# esp32_ics.net
KiCad netlist of a schematic drawn in EAGLE
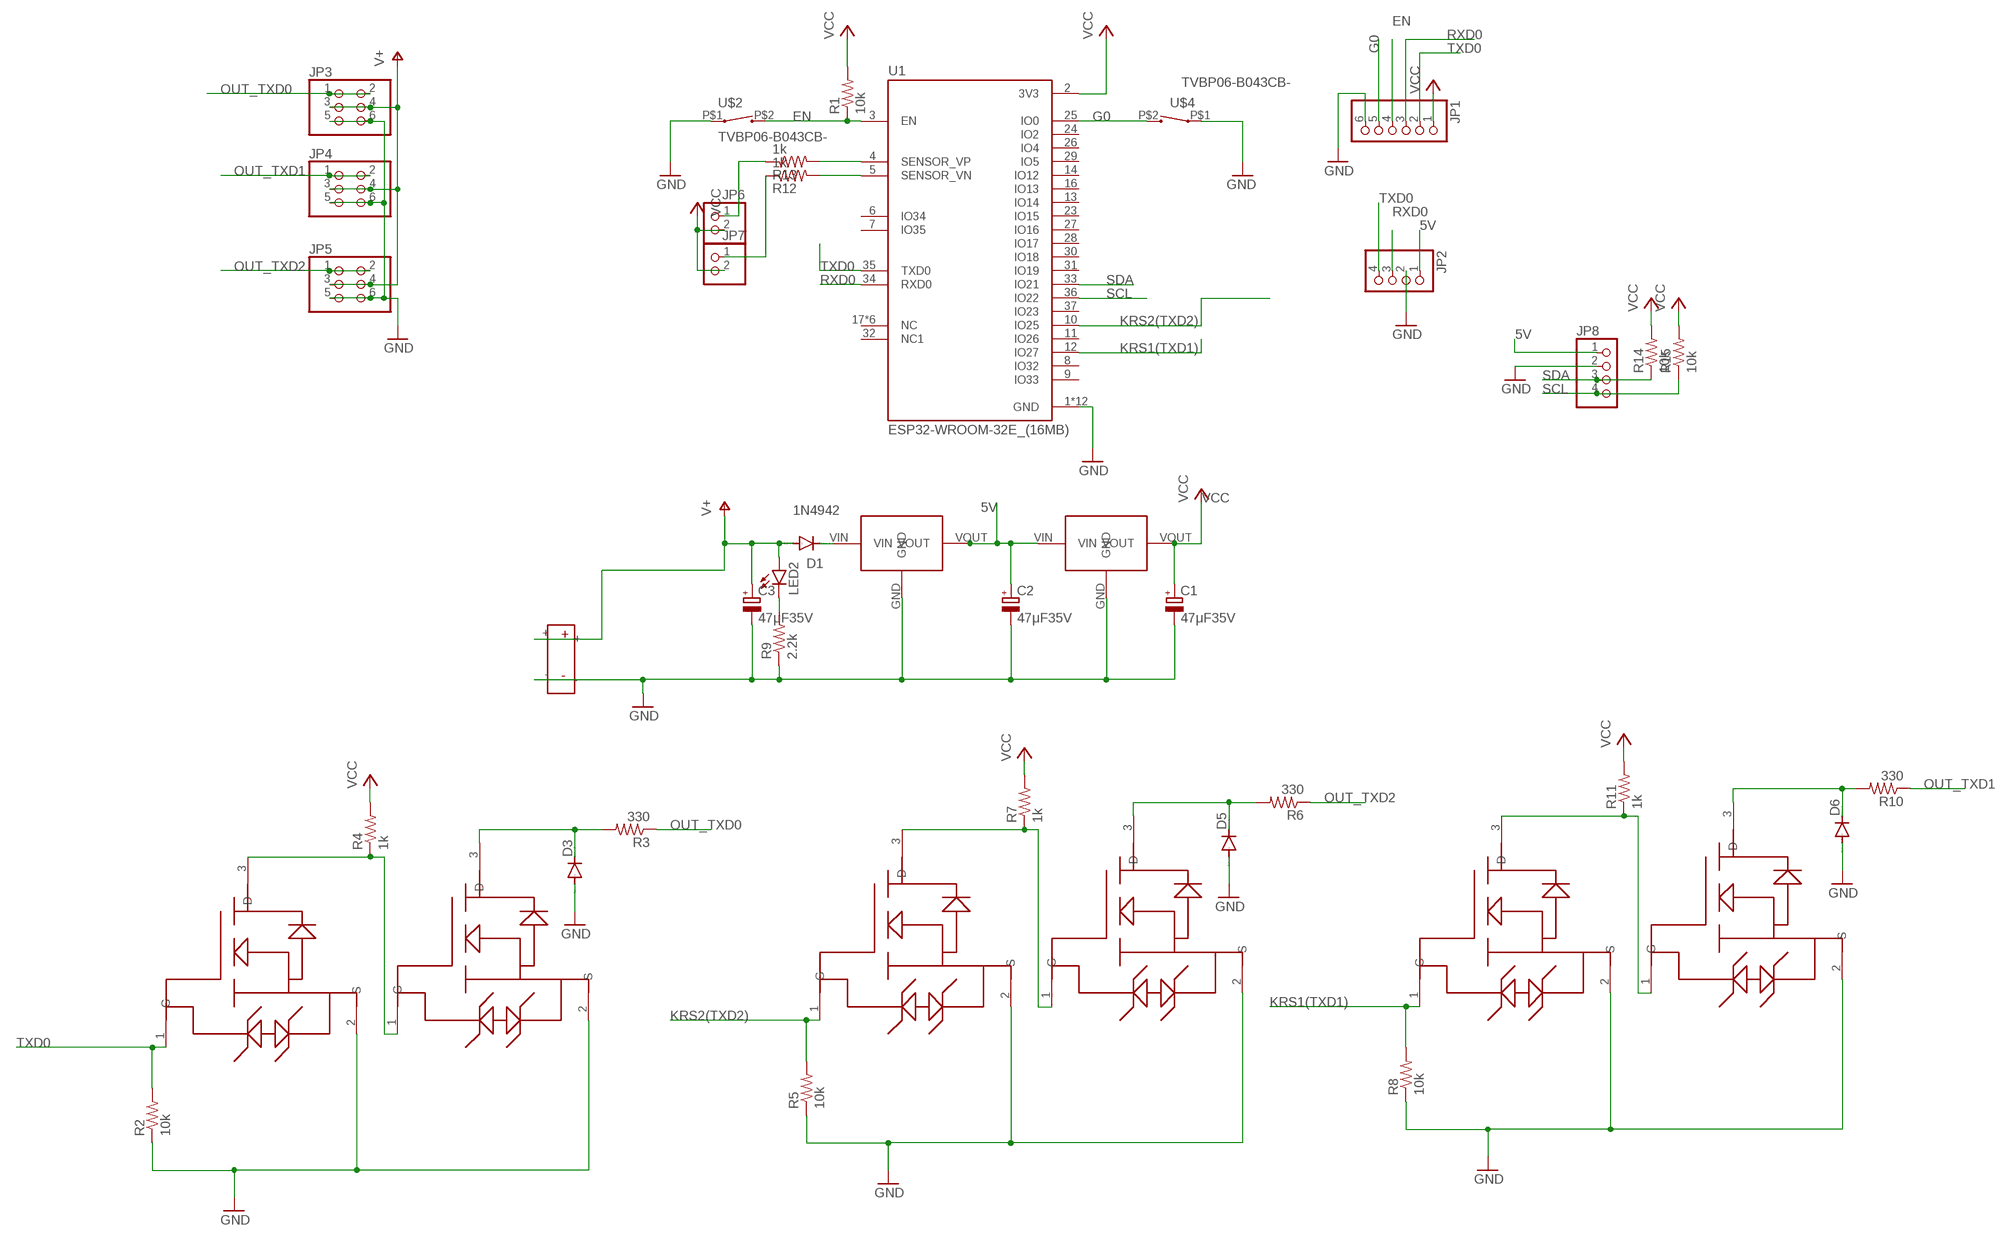
[diagram p0: schematic, sheet 1]

(export (version "E")
  (design (tool "Eeschema 10.0.6"))
  (components
    (comp (ref "C1")
      (value "47μF35V")
      (footprint "eagle-import:E2-4")
      (libsource (lib "eagle-import") (part "CPOL-EUE2-4"))
    )
    (comp (ref "C2")
      (value "47μF35V")
      (footprint "eagle-import:E2-4")
      (libsource (lib "eagle-import") (part "CPOL-EUE2-4"))
    )
    (comp (ref "C3")
      (value "47μF35V")
      (footprint "eagle-import:E2-4")
      (libsource (lib "eagle-import") (part "CPOL-EUE2-4"))
    )
    (comp (ref "D1")
      (value "1N4942")
      (footprint "eagle-import:DO41-10")
      (libsource (lib "eagle-import") (part "1N4942"))
    )
    (comp (ref "D3")
      (value "DIODE-SOD323-R")
      (footprint "eagle-import:SOD323-R")
      (libsource (lib "eagle-import") (part "DIODE-SOD323-R"))
    )
    (comp (ref "D5")
      (value "DIODE-SOD323-R")
      (footprint "eagle-import:SOD323-R")
      (libsource (lib "eagle-import") (part "DIODE-SOD323-R"))
    )
    (comp (ref "D6")
      (value "DIODE-SOD323-R")
      (footprint "eagle-import:SOD323-R")
      (libsource (lib "eagle-import") (part "DIODE-SOD323-R"))
    )
    (comp (ref "JP1")
      (value "PINHD-1X6")
      (footprint "eagle-import:1X06")
      (libsource (lib "eagle-import") (part "PINHD-1X6"))
    )
    (comp (ref "JP2")
      (value "PINHD-1X4")
      (footprint "eagle-import:1X04")
      (libsource (lib "eagle-import") (part "PINHD-1X4"))
    )
    (comp (ref "JP3")
      (value "PINHD-2X3/90")
      (footprint "eagle-import:2X03_90")
      (libsource (lib "eagle-import") (part "PINHD-2X3/90"))
    )
    (comp (ref "JP4")
      (value "PINHD-2X3/90")
      (footprint "eagle-import:2X03_90")
      (libsource (lib "eagle-import") (part "PINHD-2X3/90"))
    )
    (comp (ref "JP5")
      (value "PINHD-2X3/90")
      (footprint "eagle-import:2X03_90")
      (libsource (lib "eagle-import") (part "PINHD-2X3/90"))
    )
    (comp (ref "JP6")
      (value "PINHD-1X2")
      (footprint "eagle-import:1X02")
      (libsource (lib "eagle-import") (part "PINHD-1X2"))
    )
    (comp (ref "JP7")
      (value "PINHD-1X2")
      (footprint "eagle-import:1X02")
      (libsource (lib "eagle-import") (part "PINHD-1X2"))
    )
    (comp (ref "JP8")
      (value "PINHD-1X4")
      (footprint "eagle-import:1X04")
      (libsource (lib "eagle-import") (part "PINHD-1X4"))
    )
    (comp (ref "LED2")
      (value "LEDCHIP-LED0603")
      (footprint "eagle-import:CHIP-LED0603")
      (libsource (lib "eagle-import") (part "LEDCHIP-LED0603"))
    )
    (comp (ref "R1")
      (value "10k")
      (footprint "eagle-import:R0603")
      (libsource (lib "eagle-import") (part "R-US_R0603"))
    )
    (comp (ref "R2")
      (value "10k")
      (footprint "eagle-import:R0603")
      (libsource (lib "eagle-import") (part "R-US_R0603"))
    )
    (comp (ref "R3")
      (value "330")
      (footprint "eagle-import:R0603")
      (libsource (lib "eagle-import") (part "R-US_R0603"))
    )
    (comp (ref "R4")
      (value "1k")
      (footprint "eagle-import:R0603")
      (libsource (lib "eagle-import") (part "R-US_R0603"))
    )
    (comp (ref "R5")
      (value "10k")
      (footprint "eagle-import:R0603")
      (libsource (lib "eagle-import") (part "R-US_R0603"))
    )
    (comp (ref "R6")
      (value "330")
      (footprint "eagle-import:R0603")
      (libsource (lib "eagle-import") (part "R-US_R0603"))
    )
    (comp (ref "R7")
      (value "1k")
      (footprint "eagle-import:R0603")
      (libsource (lib "eagle-import") (part "R-US_R0603"))
    )
    (comp (ref "R8")
      (value "10k")
      (footprint "eagle-import:R0603")
      (libsource (lib "eagle-import") (part "R-US_R0603"))
    )
    (comp (ref "R9")
      (value "2.2k")
      (footprint "eagle-import:R0603")
      (libsource (lib "eagle-import") (part "R-US_R0603"))
    )
    (comp (ref "R10")
      (value "330")
      (footprint "eagle-import:R0603")
      (libsource (lib "eagle-import") (part "R-US_R0603"))
    )
    (comp (ref "R11")
      (value "1k")
      (footprint "eagle-import:R0603")
      (libsource (lib "eagle-import") (part "R-US_R0603"))
    )
    (comp (ref "R12")
      (value "1k")
      (footprint "eagle-import:R0603")
      (libsource (lib "eagle-import") (part "R-US_R0603"))
    )
    (comp (ref "R13")
      (value "1k")
      (footprint "eagle-import:R0603")
      (libsource (lib "eagle-import") (part "R-US_R0603"))
    )
    (comp (ref "R14")
      (value "10k")
      (footprint "eagle-import:R0603")
      (libsource (lib "eagle-import") (part "R-US_R0603"))
    )
    (comp (ref "R15")
      (value "10k")
      (footprint "eagle-import:R0603")
      (libsource (lib "eagle-import") (part "R-US_R0603"))
    )
    (comp (ref "U$1")
      (value "BATT")
      (footprint "eagle-import:BATT")
      (libsource (lib "eagle-import") (part "BATT"))
    )
    (comp (ref "U$2")
      (value "TVBP06-B043CB-")
      (footprint "eagle-import:TVBP06-B043CB-")
      (libsource (lib "eagle-import") (part "TVBP06-B043CB-"))
    )
    (comp (ref "U$4")
      (value "TVBP06-B043CB-")
      (footprint "eagle-import:TVBP06-B043CB-")
      (libsource (lib "eagle-import") (part "TVBP06-B043CB-"))
    )
    (comp (ref "U$5")
      (value "BSS138")
      (footprint "eagle-import:SOT23")
      (libsource (lib "eagle-import") (part "BSS138"))
    )
    (comp (ref "U$6")
      (value "BSS138")
      (footprint "eagle-import:SOT23")
      (libsource (lib "eagle-import") (part "BSS138"))
    )
    (comp (ref "U$7")
      (value "BSS138")
      (footprint "eagle-import:SOT23")
      (libsource (lib "eagle-import") (part "BSS138"))
    )
    (comp (ref "U$8")
      (value "BSS138")
      (footprint "eagle-import:SOT23")
      (libsource (lib "eagle-import") (part "BSS138"))
    )
    (comp (ref "U$9")
      (value "BSS138")
      (footprint "eagle-import:SOT23")
      (libsource (lib "eagle-import") (part "BSS138"))
    )
    (comp (ref "U$10")
      (value "BSS138")
      (footprint "eagle-import:SOT23")
      (libsource (lib "eagle-import") (part "BSS138"))
    )
    (comp (ref "U1")
      (value "ESP32-WROOM-32E_(16MB)")
      (footprint "eagle-import:XCVR_ESP32-WROOM-32E_(16MB)")
      (fields (field (name "MF") "Espressif Systems") (field (name "MP") "ESP32-WROOM-32E (16MB)"))
      (libsource (lib "eagle-import") (part "ESP32-WROOM-32E_(16MB)"))
    )
    (comp (ref "ＮＪＭ２８４５ＤＬ１")
      (value "3.3v")
      (footprint "eagle-import:TIP_3TANSI")
      (libsource (lib "eagle-import") (part "TIP_3TANSI"))
    )
    (comp (ref "ＮＪＭ７８０５ＳＤＬ１")
      (value "5v")
      (footprint "eagle-import:TIP_3TANSI")
      (libsource (lib "eagle-import") (part "TIP_3TANSI"))
    )
  )
  (nets
    (net (code "1") (name "/5V") (class "Default")
      (node (ref "C2") (pin "+") (pinfunction "+_+") (pintype "passive"))
      (node (ref "JP2") (pin "1") (pinfunction "1_1") (pintype "passive"))
      (node (ref "JP8") (pin "1") (pinfunction "1_1") (pintype "passive"))
      (node (ref "ＮＪＭ２８４５ＤＬ１") (pin "VIN") (pinfunction "VIN_VIN") (pintype "bidirectional"))
      (node (ref "ＮＪＭ７８０５ＳＤＬ１") (pin "VOUT") (pinfunction "VOUT_VOUT") (pintype "bidirectional"))
    )
    (net (code "2") (name "/EN") (class "Default")
      (node (ref "JP1") (pin "4") (pinfunction "4_4") (pintype "passive"))
      (node (ref "R1") (pin "1") (pinfunction "1_1") (pintype "passive"))
      (node (ref "U$2") (pin "P$2") (pinfunction "2_P$2") (pintype "passive"))
      (node (ref "U1") (pin "3") (pinfunction "EN_3") (pintype "input"))
    )
    (net (code "3") (name "/G0") (class "Default")
      (node (ref "JP1") (pin "5") (pinfunction "5_5") (pintype "passive"))
      (node (ref "U$4") (pin "P$2") (pinfunction "2_P$2") (pintype "passive"))
      (node (ref "U1") (pin "25") (pinfunction "IO0_25") (pintype "bidirectional"))
    )
    (net (code "4") (name "/KRS1(TXD1)") (class "Default")
      (node (ref "R8") (pin "2") (pinfunction "2_2") (pintype "passive"))
      (node (ref "U$9") (pin "1") (pinfunction "G_1") (pintype "bidirectional"))
      (node (ref "U1") (pin "12") (pinfunction "IO27_12") (pintype "bidirectional"))
    )
    (net (code "5") (name "/KRS2(TXD2)") (class "Default")
      (node (ref "R5") (pin "2") (pinfunction "2_2") (pintype "passive"))
      (node (ref "U$5") (pin "1") (pinfunction "G_1") (pintype "bidirectional"))
      (node (ref "U1") (pin "10") (pinfunction "IO25_10") (pintype "bidirectional"))
    )
    (net (code "6") (name "/OUT_TXD0") (class "Default")
      (node (ref "JP3") (pin "1") (pinfunction "1_1") (pintype "passive"))
      (node (ref "JP3") (pin "2") (pinfunction "2_2") (pintype "passive"))
      (node (ref "R3") (pin "1") (pinfunction "1_1") (pintype "passive"))
    )
    (net (code "7") (name "/OUT_TXD1") (class "Default")
      (node (ref "JP4") (pin "1") (pinfunction "1_1") (pintype "passive"))
      (node (ref "JP4") (pin "2") (pinfunction "2_2") (pintype "passive"))
      (node (ref "R10") (pin "1") (pinfunction "1_1") (pintype "passive"))
    )
    (net (code "8") (name "/OUT_TXD2") (class "Default")
      (node (ref "JP5") (pin "1") (pinfunction "1_1") (pintype "passive"))
      (node (ref "JP5") (pin "2") (pinfunction "2_2") (pintype "passive"))
      (node (ref "R6") (pin "1") (pinfunction "1_1") (pintype "passive"))
    )
    (net (code "9") (name "/RXD0") (class "Default")
      (node (ref "JP1") (pin "3") (pinfunction "3_3") (pintype "passive"))
      (node (ref "JP2") (pin "3") (pinfunction "3_3") (pintype "passive"))
      (node (ref "U1") (pin "34") (pinfunction "RXD0_34") (pintype "bidirectional"))
    )
    (net (code "10") (name "/SCL") (class "Default")
      (node (ref "JP8") (pin "4") (pinfunction "4_4") (pintype "passive"))
      (node (ref "R15") (pin "1") (pinfunction "1_1") (pintype "passive"))
      (node (ref "U1") (pin "36") (pinfunction "IO22_36") (pintype "bidirectional"))
    )
    (net (code "11") (name "/SDA") (class "Default")
      (node (ref "JP8") (pin "3") (pinfunction "3_3") (pintype "passive"))
      (node (ref "R14") (pin "1") (pinfunction "1_1") (pintype "passive"))
      (node (ref "U1") (pin "33") (pinfunction "IO21_33") (pintype "bidirectional"))
    )
    (net (code "12") (name "/TXD0") (class "Default")
      (node (ref "JP1") (pin "2") (pinfunction "2_2") (pintype "passive"))
      (node (ref "JP2") (pin "4") (pinfunction "4_4") (pintype "passive"))
      (node (ref "R2") (pin "2") (pinfunction "2_2") (pintype "passive"))
      (node (ref "U$7") (pin "1") (pinfunction "G_1") (pintype "bidirectional"))
      (node (ref "U1") (pin "35") (pinfunction "TXD0_35") (pintype "bidirectional"))
    )
    (net (code "13") (name "GND") (class "Default")
      (node (ref "C1") (pin "-") (pinfunction "-_-") (pintype "passive"))
      (node (ref "C2") (pin "-") (pinfunction "-_-") (pintype "passive"))
      (node (ref "C3") (pin "-") (pinfunction "-_-") (pintype "passive"))
      (node (ref "D3") (pin "A") (pinfunction "A_A") (pintype "passive"))
      (node (ref "D5") (pin "A") (pinfunction "A_A") (pintype "passive"))
      (node (ref "D6") (pin "A") (pinfunction "A_A") (pintype "passive"))
      (node (ref "JP1") (pin "6") (pinfunction "6_6") (pintype "passive"))
      (node (ref "JP2") (pin "2") (pinfunction "2_2") (pintype "passive"))
      (node (ref "JP3") (pin "5") (pinfunction "5_5") (pintype "passive"))
      (node (ref "JP3") (pin "6") (pinfunction "6_6") (pintype "passive"))
      (node (ref "JP4") (pin "5") (pinfunction "5_5") (pintype "passive"))
      (node (ref "JP4") (pin "6") (pinfunction "6_6") (pintype "passive"))
      (node (ref "JP5") (pin "5") (pinfunction "5_5") (pintype "passive"))
      (node (ref "JP5") (pin "6") (pinfunction "6_6") (pintype "passive"))
      (node (ref "JP8") (pin "2") (pinfunction "2_2") (pintype "passive"))
      (node (ref "R2") (pin "1") (pinfunction "1_1") (pintype "passive"))
      (node (ref "R5") (pin "1") (pinfunction "1_1") (pintype "passive"))
      (node (ref "R8") (pin "1") (pinfunction "1_1") (pintype "passive"))
      (node (ref "R9") (pin "1") (pinfunction "1_1") (pintype "passive"))
      (node (ref "U$1") (pin "-") (pinfunction "-_-") (pintype "bidirectional"))
      (node (ref "U$10") (pin "2") (pinfunction "S_2") (pintype "bidirectional"))
      (node (ref "U$2") (pin "P$1") (pinfunction "1_P$1") (pintype "passive"))
      (node (ref "U$4") (pin "P$1") (pinfunction "1_P$1") (pintype "passive"))
      (node (ref "U$5") (pin "2") (pinfunction "S_2") (pintype "bidirectional"))
      (node (ref "U$6") (pin "2") (pinfunction "S_2") (pintype "bidirectional"))
      (node (ref "U$7") (pin "2") (pinfunction "S_2") (pintype "bidirectional"))
      (node (ref "U$8") (pin "2") (pinfunction "S_2") (pintype "bidirectional"))
      (node (ref "U$9") (pin "2") (pinfunction "S_2") (pintype "bidirectional"))
      (node (ref "U1") (pin "1") (pinfunction "GND_1") (pintype "power_in"))
      (node (ref "U1") (pin "15") (pinfunction "GND_15") (pintype "power_in"))
      (node (ref "U1") (pin "38") (pinfunction "GND_38") (pintype "power_in"))
      (node (ref "U1") (pin "39_1") (pinfunction "GND_39_1") (pintype "power_in"))
      (node (ref "U1") (pin "39_2") (pinfunction "GND_39_2") (pintype "power_in"))
      (node (ref "U1") (pin "39_3") (pinfunction "GND_39_3") (pintype "power_in"))
      (node (ref "U1") (pin "39_4") (pinfunction "GND_39_4") (pintype "power_in"))
      (node (ref "U1") (pin "39_5") (pinfunction "GND_39_5") (pintype "power_in"))
      (node (ref "U1") (pin "39_6") (pinfunction "GND_39_6") (pintype "power_in"))
      (node (ref "U1") (pin "39_7") (pinfunction "GND_39_7") (pintype "power_in"))
      (node (ref "U1") (pin "39_8") (pinfunction "GND_39_8") (pintype "power_in"))
      (node (ref "U1") (pin "39_9") (pinfunction "GND_39_9") (pintype "power_in"))
      (node (ref "ＮＪＭ２８４５ＤＬ１") (pin "GND") (pinfunction "GND_GND") (pintype "bidirectional"))
      (node (ref "ＮＪＭ７８０５ＳＤＬ１") (pin "GND") (pinfunction "GND_GND") (pintype "bidirectional"))
    )
    (net (code "14") (name "Net-(D1-PadC)") (class "Default")
      (node (ref "D1") (pin "C") (pinfunction "C_C") (pintype "passive"))
      (node (ref "ＮＪＭ７８０５ＳＤＬ１") (pin "VIN") (pinfunction "VIN_VIN") (pintype "bidirectional"))
    )
    (net (code "15") (name "Net-(JP6-Pad1)") (class "Default")
      (node (ref "JP6") (pin "1") (pinfunction "1_1") (pintype "passive"))
      (node (ref "R13") (pin "1") (pinfunction "1_1") (pintype "passive"))
    )
    (net (code "16") (name "Net-(JP7-Pad1)") (class "Default")
      (node (ref "JP7") (pin "1") (pinfunction "1_1") (pintype "passive"))
      (node (ref "R12") (pin "1") (pinfunction "1_1") (pintype "passive"))
    )
    (net (code "17") (name "Net-(LED2-PadC)") (class "Default")
      (node (ref "LED2") (pin "C") (pinfunction "C_C") (pintype "passive"))
      (node (ref "R9") (pin "2") (pinfunction "2_2") (pintype "passive"))
    )
    (net (code "18") (name "Net-(U$5-D)") (class "Default")
      (node (ref "R7") (pin "1") (pinfunction "1_1") (pintype "passive"))
      (node (ref "U$5") (pin "3") (pinfunction "D_3") (pintype "bidirectional"))
      (node (ref "U$6") (pin "1") (pinfunction "G_1") (pintype "bidirectional"))
    )
    (net (code "19") (name "Net-(U$6-D)") (class "Default")
      (node (ref "D5") (pin "C") (pinfunction "C_C") (pintype "passive"))
      (node (ref "R6") (pin "2") (pinfunction "2_2") (pintype "passive"))
      (node (ref "U$6") (pin "3") (pinfunction "D_3") (pintype "bidirectional"))
    )
    (net (code "20") (name "Net-(U$7-D)") (class "Default")
      (node (ref "R4") (pin "1") (pinfunction "1_1") (pintype "passive"))
      (node (ref "U$7") (pin "3") (pinfunction "D_3") (pintype "bidirectional"))
      (node (ref "U$8") (pin "1") (pinfunction "G_1") (pintype "bidirectional"))
    )
    (net (code "21") (name "Net-(U$8-D)") (class "Default")
      (node (ref "D3") (pin "C") (pinfunction "C_C") (pintype "passive"))
      (node (ref "R3") (pin "2") (pinfunction "2_2") (pintype "passive"))
      (node (ref "U$8") (pin "3") (pinfunction "D_3") (pintype "bidirectional"))
    )
    (net (code "22") (name "Net-(U$10-D)") (class "Default")
      (node (ref "D6") (pin "C") (pinfunction "C_C") (pintype "passive"))
      (node (ref "R10") (pin "2") (pinfunction "2_2") (pintype "passive"))
      (node (ref "U$10") (pin "3") (pinfunction "D_3") (pintype "bidirectional"))
    )
    (net (code "23") (name "Net-(U$10-G)") (class "Default")
      (node (ref "R11") (pin "1") (pinfunction "1_1") (pintype "passive"))
      (node (ref "U$10") (pin "1") (pinfunction "G_1") (pintype "bidirectional"))
      (node (ref "U$9") (pin "3") (pinfunction "D_3") (pintype "bidirectional"))
    )
    (net (code "24") (name "Net-(U1-SENSOR_VN)") (class "Default")
      (node (ref "R12") (pin "2") (pinfunction "2_2") (pintype "passive"))
      (node (ref "U1") (pin "5") (pinfunction "SENSOR_VN_5") (pintype "input"))
    )
    (net (code "25") (name "Net-(U1-SENSOR_VP)") (class "Default")
      (node (ref "R13") (pin "2") (pinfunction "2_2") (pintype "passive"))
      (node (ref "U1") (pin "4") (pinfunction "SENSOR_VP_4") (pintype "input"))
    )
    (net (code "26") (name "V+") (class "Default")
      (node (ref "C3") (pin "+") (pinfunction "+_+") (pintype "passive"))
      (node (ref "D1") (pin "A") (pinfunction "A_A") (pintype "passive"))
      (node (ref "JP3") (pin "3") (pinfunction "3_3") (pintype "passive"))
      (node (ref "JP3") (pin "4") (pinfunction "4_4") (pintype "passive"))
      (node (ref "JP4") (pin "3") (pinfunction "3_3") (pintype "passive"))
      (node (ref "JP4") (pin "4") (pinfunction "4_4") (pintype "passive"))
      (node (ref "JP5") (pin "3") (pinfunction "3_3") (pintype "passive"))
      (node (ref "JP5") (pin "4") (pinfunction "4_4") (pintype "passive"))
      (node (ref "LED2") (pin "A") (pinfunction "A_A") (pintype "passive"))
      (node (ref "U$1") (pin "+") (pinfunction "+_+") (pintype "bidirectional"))
    )
    (net (code "27") (name "VCC") (class "Default")
      (node (ref "C1") (pin "+") (pinfunction "+_+") (pintype "passive"))
      (node (ref "JP1") (pin "1") (pinfunction "1_1") (pintype "passive"))
      (node (ref "JP6") (pin "2") (pinfunction "2_2") (pintype "passive"))
      (node (ref "JP7") (pin "2") (pinfunction "2_2") (pintype "passive"))
      (node (ref "R1") (pin "2") (pinfunction "2_2") (pintype "passive"))
      (node (ref "R11") (pin "2") (pinfunction "2_2") (pintype "passive"))
      (node (ref "R14") (pin "2") (pinfunction "2_2") (pintype "passive"))
      (node (ref "R15") (pin "2") (pinfunction "2_2") (pintype "passive"))
      (node (ref "R4") (pin "2") (pinfunction "2_2") (pintype "passive"))
      (node (ref "R7") (pin "2") (pinfunction "2_2") (pintype "passive"))
      (node (ref "U1") (pin "2") (pinfunction "3V3_2") (pintype "power_in"))
      (node (ref "ＮＪＭ２８４５ＤＬ１") (pin "VOUT") (pinfunction "VOUT_VOUT") (pintype "bidirectional"))
    )
    (net (code "28") (name "unconnected-(U1-IO2-Pad24)") (class "Default")
      (node (ref "U1") (pin "24") (pinfunction "IO2_24") (pintype "bidirectional"))
    )
    (net (code "29") (name "unconnected-(U1-IO4-Pad26)") (class "Default")
      (node (ref "U1") (pin "26") (pinfunction "IO4_26") (pintype "bidirectional"))
    )
    (net (code "30") (name "unconnected-(U1-IO5-Pad29)") (class "Default")
      (node (ref "U1") (pin "29") (pinfunction "IO5_29") (pintype "bidirectional"))
    )
    (net (code "31") (name "unconnected-(U1-IO12-Pad14)") (class "Default")
      (node (ref "U1") (pin "14") (pinfunction "IO12_14") (pintype "bidirectional"))
    )
    (net (code "32") (name "unconnected-(U1-IO13-Pad16)") (class "Default")
      (node (ref "U1") (pin "16") (pinfunction "IO13_16") (pintype "bidirectional"))
    )
    (net (code "33") (name "unconnected-(U1-IO14-Pad13)") (class "Default")
      (node (ref "U1") (pin "13") (pinfunction "IO14_13") (pintype "bidirectional"))
    )
    (net (code "34") (name "unconnected-(U1-IO15-Pad23)") (class "Default")
      (node (ref "U1") (pin "23") (pinfunction "IO15_23") (pintype "bidirectional"))
    )
    (net (code "35") (name "unconnected-(U1-IO16-Pad27)") (class "Default")
      (node (ref "U1") (pin "27") (pinfunction "IO16_27") (pintype "bidirectional"))
    )
    (net (code "36") (name "unconnected-(U1-IO17-Pad28)") (class "Default")
      (node (ref "U1") (pin "28") (pinfunction "IO17_28") (pintype "bidirectional"))
    )
    (net (code "37") (name "unconnected-(U1-IO18-Pad30)") (class "Default")
      (node (ref "U1") (pin "30") (pinfunction "IO18_30") (pintype "bidirectional"))
    )
    (net (code "38") (name "unconnected-(U1-IO19-Pad31)") (class "Default")
      (node (ref "U1") (pin "31") (pinfunction "IO19_31") (pintype "bidirectional"))
    )
    (net (code "39") (name "unconnected-(U1-IO23-Pad37)") (class "Default")
      (node (ref "U1") (pin "37") (pinfunction "IO23_37") (pintype "bidirectional"))
    )
    (net (code "40") (name "unconnected-(U1-IO26-Pad11)") (class "Default")
      (node (ref "U1") (pin "11") (pinfunction "IO26_11") (pintype "bidirectional"))
    )
    (net (code "41") (name "unconnected-(U1-IO32-Pad8)") (class "Default")
      (node (ref "U1") (pin "8") (pinfunction "IO32_8") (pintype "bidirectional"))
    )
    (net (code "42") (name "unconnected-(U1-IO33-Pad9)") (class "Default")
      (node (ref "U1") (pin "9") (pinfunction "IO33_9") (pintype "bidirectional"))
    )
    (net (code "43") (name "unconnected-(U1-IO34-Pad6)") (class "Default")
      (node (ref "U1") (pin "6") (pinfunction "IO34_6") (pintype "input"))
    )
    (net (code "44") (name "unconnected-(U1-IO35-Pad7)") (class "Default")
      (node (ref "U1") (pin "7") (pinfunction "IO35_7") (pintype "input"))
    )
    (net (code "45") (name "unconnected-(U1-NC-Pad17)") (class "Default")
      (node (ref "U1") (pin "17") (pinfunction "NC_17") (pintype "no_connect"))
    )
    (net (code "46") (name "unconnected-(U1-NC-Pad18)") (class "Default")
      (node (ref "U1") (pin "18") (pinfunction "NC_18") (pintype "no_connect"))
    )
    (net (code "47") (name "unconnected-(U1-NC-Pad19)") (class "Default")
      (node (ref "U1") (pin "19") (pinfunction "NC_19") (pintype "no_connect"))
    )
    (net (code "48") (name "unconnected-(U1-NC-Pad20)") (class "Default")
      (node (ref "U1") (pin "20") (pinfunction "NC_20") (pintype "no_connect"))
    )
    (net (code "49") (name "unconnected-(U1-NC-Pad21)") (class "Default")
      (node (ref "U1") (pin "21") (pinfunction "NC_21") (pintype "no_connect"))
    )
    (net (code "50") (name "unconnected-(U1-NC-Pad22)") (class "Default")
      (node (ref "U1") (pin "22") (pinfunction "NC_22") (pintype "no_connect"))
    )
    (net (code "51") (name "unconnected-(U1-NC1-Pad32)") (class "Default")
      (node (ref "U1") (pin "32") (pinfunction "NC1_32") (pintype "no_connect"))
    )
  )
)
